# dcmotor_controller.net
KiCad netlist of a schematic drawn in EAGLE
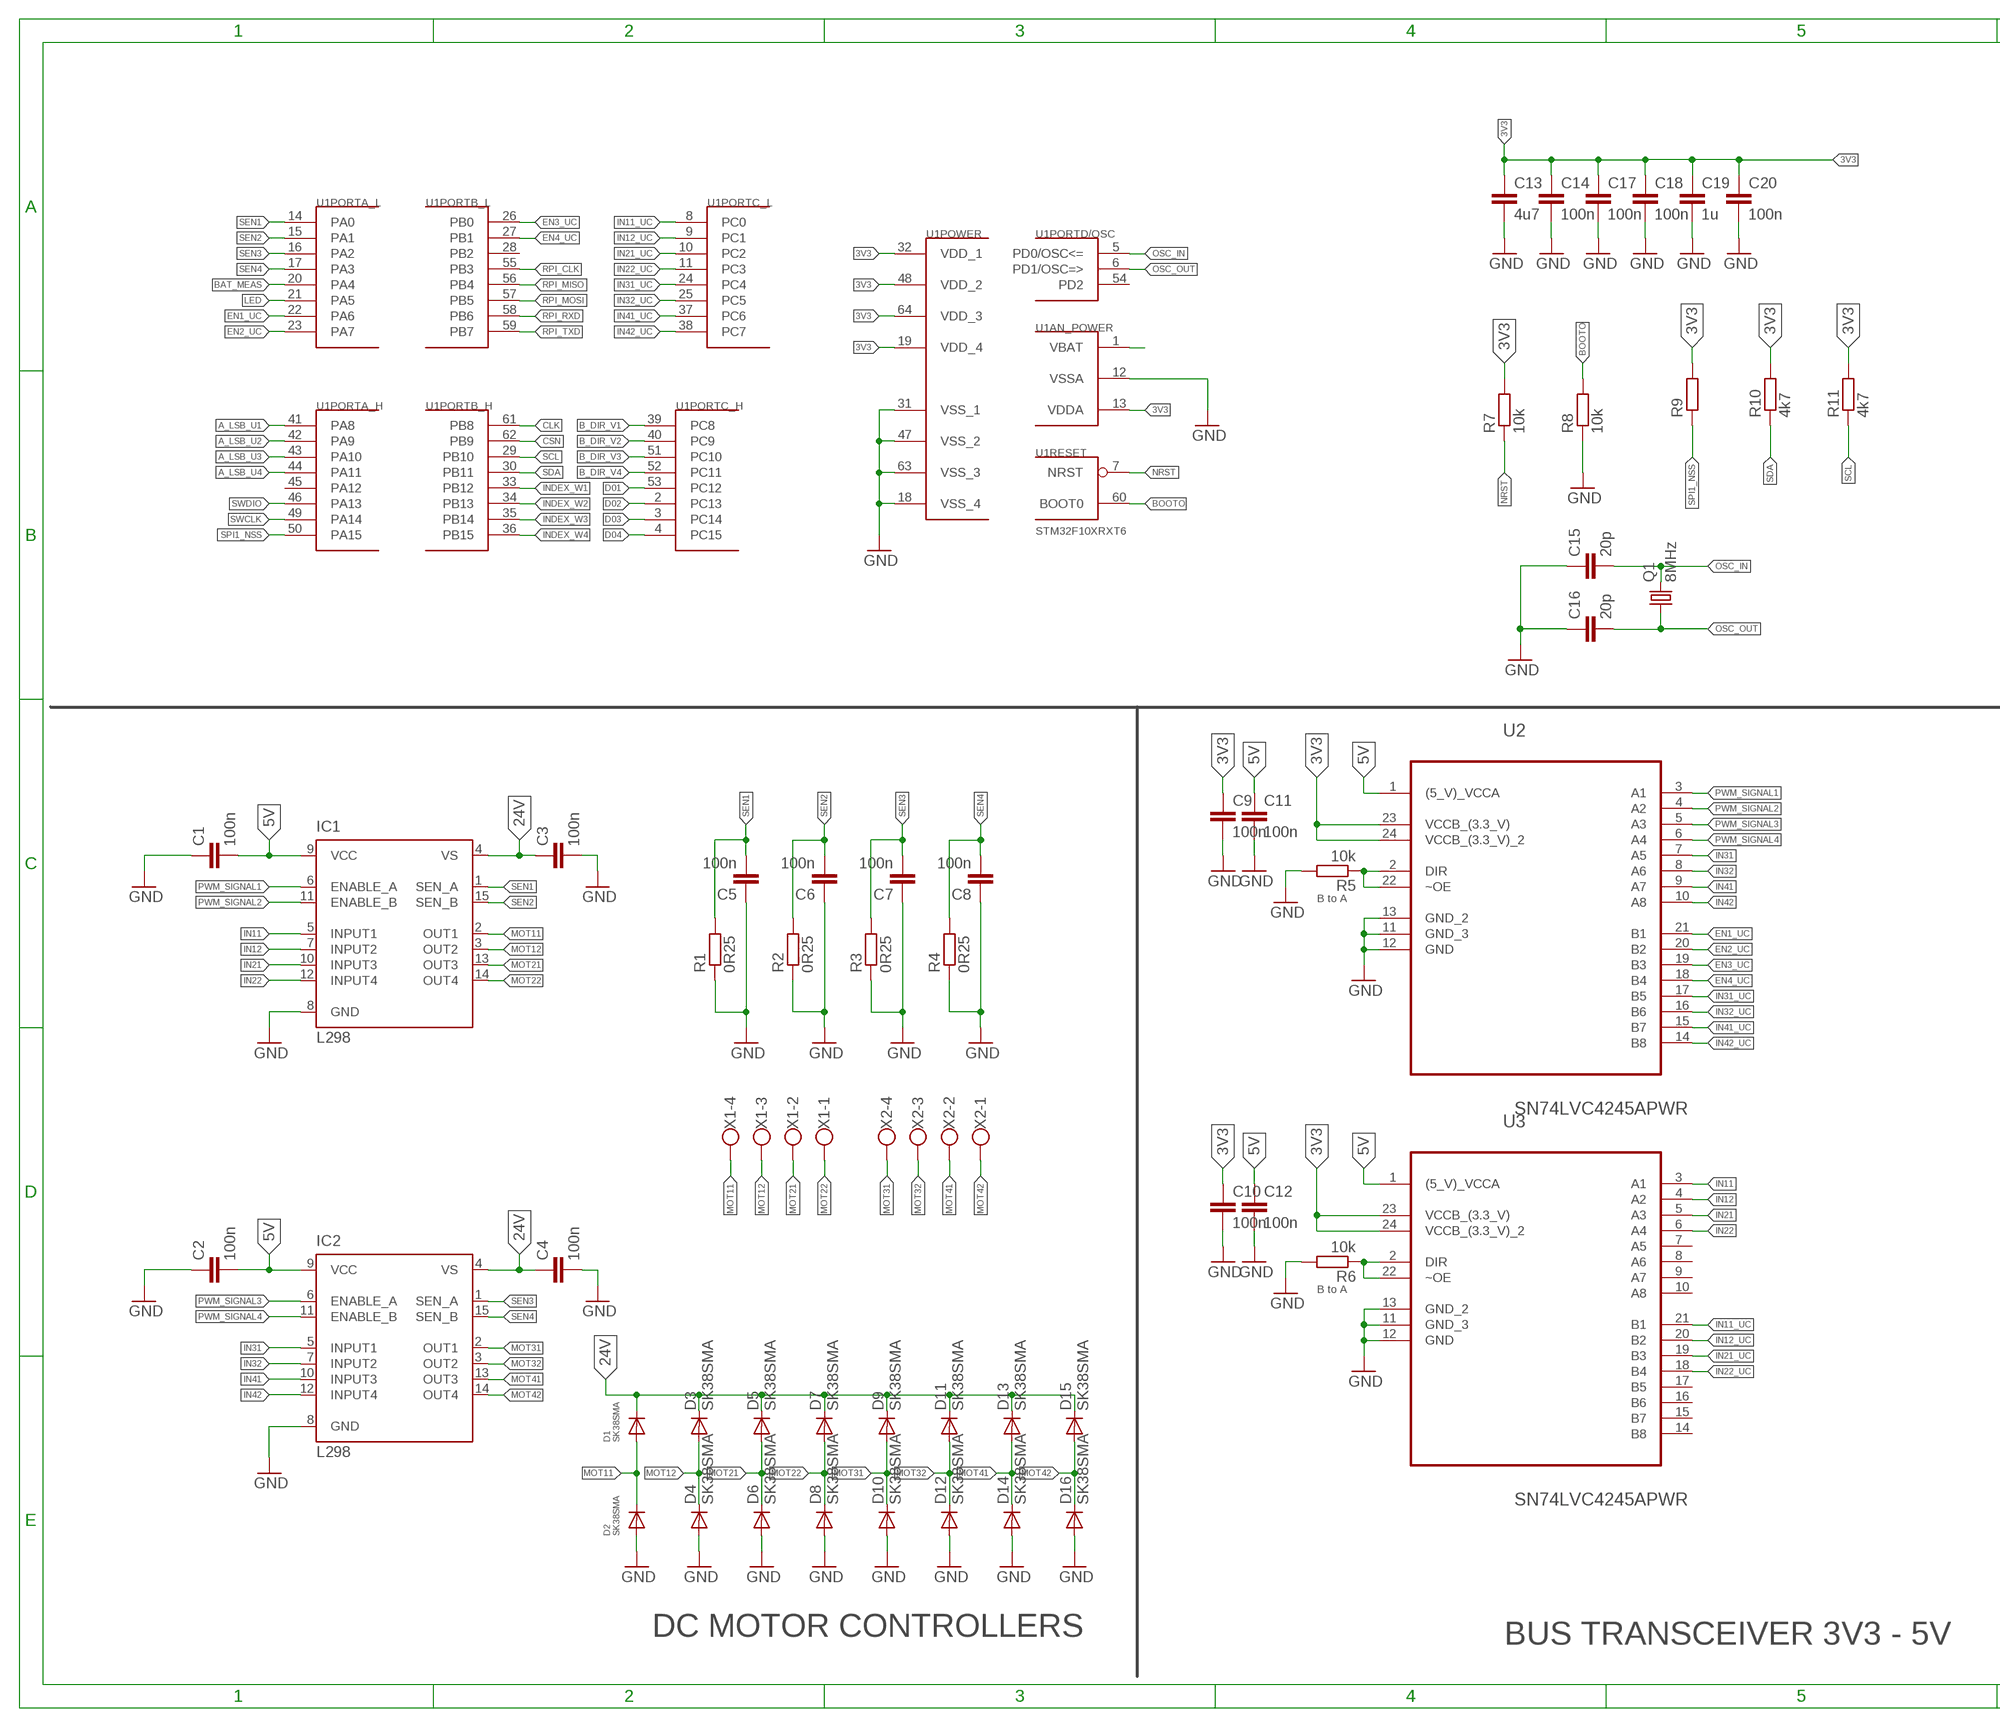
[diagram p0: schematic, sheet 1, part 1 of 2]
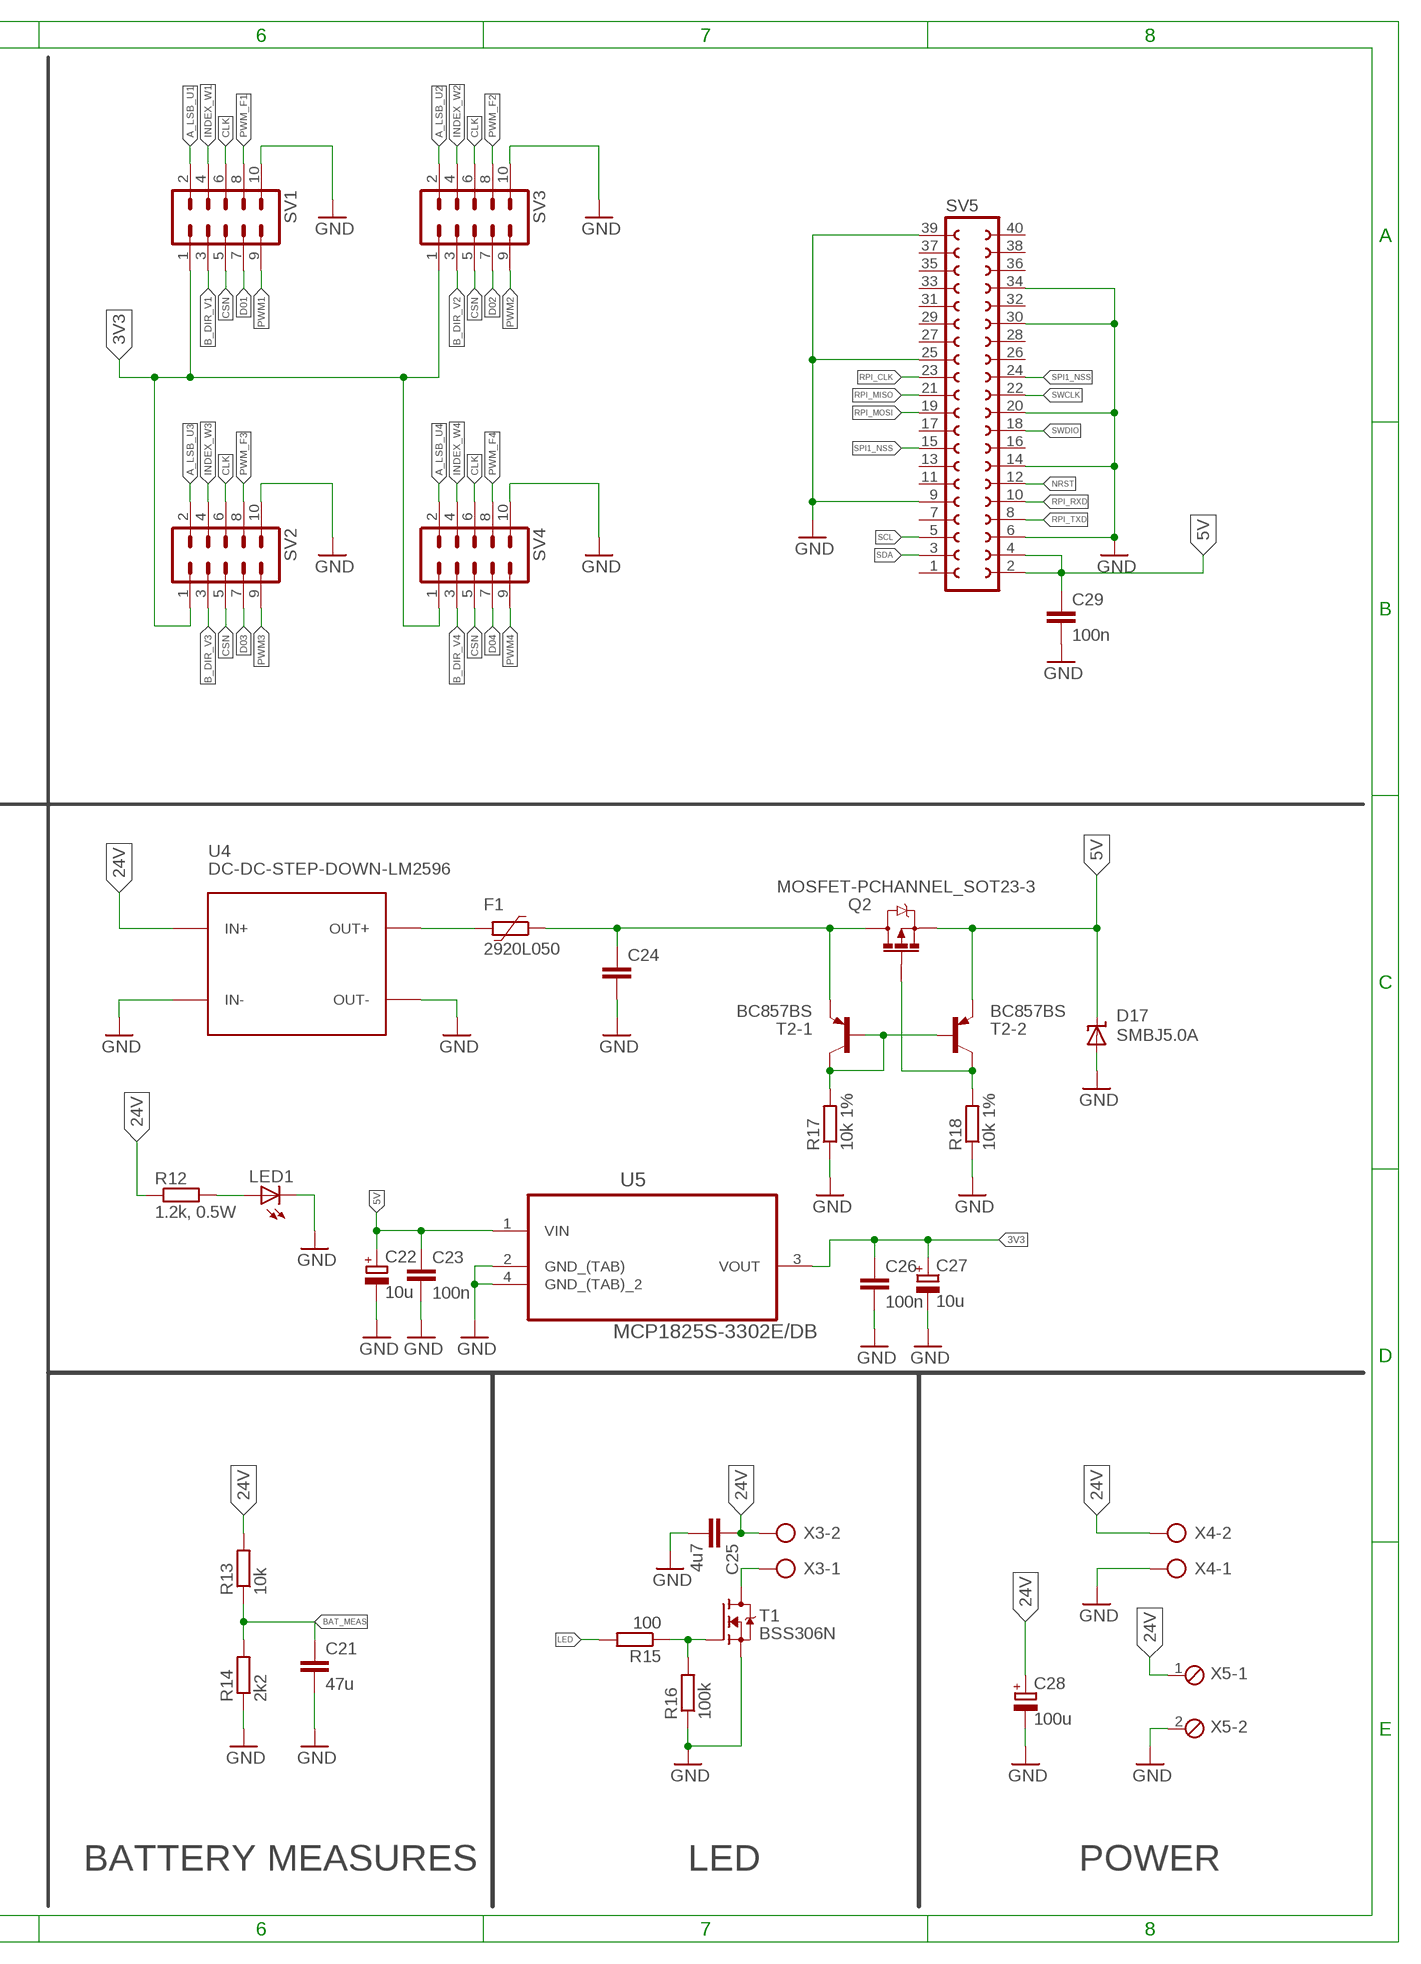
[diagram p1: schematic, sheet 1, part 2 of 2]

(export (version "E")
  (design (tool "Eeschema 10.0.6"))
  (components
    (comp (ref "C1")
      (value "100n")
      (footprint "eagle-import:C0805")
      (libsource (lib "eagle-import") (part "C-EUC0805"))
    )
    (comp (ref "C2")
      (value "100n")
      (footprint "eagle-import:C0805")
      (libsource (lib "eagle-import") (part "resistor_348_C-EUC0805"))
    )
    (comp (ref "C3")
      (value "100n")
      (footprint "eagle-import:C0805")
      (libsource (lib "eagle-import") (part "C-EUC0805"))
    )
    (comp (ref "C4")
      (value "100n")
      (footprint "eagle-import:C0805")
      (libsource (lib "eagle-import") (part "resistor_348_C-EUC0805"))
    )
    (comp (ref "C5")
      (value "100n")
      (footprint "eagle-import:C0805")
      (libsource (lib "eagle-import") (part "resistor_348_C-EUC0805"))
    )
    (comp (ref "C6")
      (value "100n")
      (footprint "eagle-import:C0805")
      (libsource (lib "eagle-import") (part "resistor_348_C-EUC0805"))
    )
    (comp (ref "C7")
      (value "100n")
      (footprint "eagle-import:C0805")
      (libsource (lib "eagle-import") (part "resistor_348_C-EUC0805"))
    )
    (comp (ref "C8")
      (value "100n")
      (footprint "eagle-import:C0805")
      (libsource (lib "eagle-import") (part "resistor_348_C-EUC0805"))
    )
    (comp (ref "C9")
      (value "100n")
      (footprint "eagle-import:C0805")
      (libsource (lib "eagle-import") (part "resistor_C-EUC0805"))
    )
    (comp (ref "C10")
      (value "100n")
      (footprint "eagle-import:C0805")
      (libsource (lib "eagle-import") (part "resistor_C-EUC0805"))
    )
    (comp (ref "C11")
      (value "100n")
      (footprint "eagle-import:C0805")
      (libsource (lib "eagle-import") (part "resistor_C-EUC0805"))
    )
    (comp (ref "C12")
      (value "100n")
      (footprint "eagle-import:C0805")
      (libsource (lib "eagle-import") (part "resistor_C-EUC0805"))
    )
    (comp (ref "C13")
      (value "4u7")
      (footprint "eagle-import:C0805")
      (libsource (lib "eagle-import") (part "C-EUC0805"))
    )
    (comp (ref "C14")
      (value "100n")
      (footprint "eagle-import:C0805")
      (libsource (lib "eagle-import") (part "C-EUC0805"))
    )
    (comp (ref "C15")
      (value "20p")
      (footprint "eagle-import:C0805")
      (libsource (lib "eagle-import") (part "C-EUC0805"))
    )
    (comp (ref "C16")
      (value "20p")
      (footprint "eagle-import:C0805")
      (libsource (lib "eagle-import") (part "C-EUC0805"))
    )
    (comp (ref "C17")
      (value "100n")
      (footprint "eagle-import:C0805")
      (libsource (lib "eagle-import") (part "C-EUC0805"))
    )
    (comp (ref "C18")
      (value "100n")
      (footprint "eagle-import:C0805")
      (libsource (lib "eagle-import") (part "C-EUC0805"))
    )
    (comp (ref "C19")
      (value "1u")
      (footprint "eagle-import:C0805")
      (libsource (lib "eagle-import") (part "C-EUC0805"))
    )
    (comp (ref "C20")
      (value "100n")
      (footprint "eagle-import:C0805")
      (libsource (lib "eagle-import") (part "C-EUC0805"))
    )
    (comp (ref "C21")
      (value "47u")
      (footprint "eagle-import:C0805")
      (libsource (lib "eagle-import") (part "resistor_348_C-EUC0805"))
    )
    (comp (ref "C22")
      (value "10u")
      (footprint "eagle-import:153CLV-0807")
      (libsource (lib "eagle-import") (part "CPOL-EU153CLV-0807"))
    )
    (comp (ref "C23")
      (value "100n")
      (footprint "eagle-import:C0805")
      (libsource (lib "eagle-import") (part "resistor_348_C-EUC0805"))
    )
    (comp (ref "C24")
      (value "C-EUC0805")
      (footprint "eagle-import:C0805")
      (libsource (lib "eagle-import") (part "C-EUC0805"))
    )
    (comp (ref "C25")
      (value "4u7")
      (footprint "eagle-import:C0805")
      (libsource (lib "eagle-import") (part "resistor_348_C-EUC0805"))
    )
    (comp (ref "C26")
      (value "100n")
      (footprint "eagle-import:C0805")
      (libsource (lib "eagle-import") (part "resistor_348_C-EUC0805"))
    )
    (comp (ref "C27")
      (value "10u")
      (footprint "eagle-import:153CLV-0807")
      (libsource (lib "eagle-import") (part "CPOL-EU153CLV-0807"))
    )
    (comp (ref "C28")
      (value "100u")
      (footprint "eagle-import:153CLV-0807")
      (libsource (lib "eagle-import") (part "CPOL-EU153CLV-0807"))
    )
    (comp (ref "C29")
      (value "100n")
      (footprint "eagle-import:C0805")
      (libsource (lib "eagle-import") (part "resistor_348_C-EUC0805"))
    )
    (comp (ref "D1")
      (value "SK38SMA")
      (footprint "eagle-import:DO214AC")
      (libsource (lib "eagle-import") (part "DIODE-DO214AC"))
    )
    (comp (ref "D2")
      (value "SK38SMA")
      (footprint "eagle-import:DO214AC")
      (libsource (lib "eagle-import") (part "DIODE-DO214AC"))
    )
    (comp (ref "D3")
      (value "SK38SMA")
      (footprint "eagle-import:DO214AC")
      (libsource (lib "eagle-import") (part "DIODE-DO214AC"))
    )
    (comp (ref "D4")
      (value "SK38SMA")
      (footprint "eagle-import:DO214AC")
      (libsource (lib "eagle-import") (part "DIODE-DO214AC"))
    )
    (comp (ref "D5")
      (value "SK38SMA")
      (footprint "eagle-import:DO214AC")
      (libsource (lib "eagle-import") (part "DIODE-DO214AC"))
    )
    (comp (ref "D6")
      (value "SK38SMA")
      (footprint "eagle-import:DO214AC")
      (libsource (lib "eagle-import") (part "DIODE-DO214AC"))
    )
    (comp (ref "D7")
      (value "SK38SMA")
      (footprint "eagle-import:DO214AC")
      (libsource (lib "eagle-import") (part "DIODE-DO214AC"))
    )
    (comp (ref "D8")
      (value "SK38SMA")
      (footprint "eagle-import:DO214AC")
      (libsource (lib "eagle-import") (part "DIODE-DO214AC"))
    )
    (comp (ref "D9")
      (value "SK38SMA")
      (footprint "eagle-import:DO214AC")
      (libsource (lib "eagle-import") (part "DIODE-DO214AC"))
    )
    (comp (ref "D10")
      (value "SK38SMA")
      (footprint "eagle-import:DO214AC")
      (libsource (lib "eagle-import") (part "DIODE-DO214AC"))
    )
    (comp (ref "D11")
      (value "SK38SMA")
      (footprint "eagle-import:DO214AC")
      (libsource (lib "eagle-import") (part "DIODE-DO214AC"))
    )
    (comp (ref "D12")
      (value "SK38SMA")
      (footprint "eagle-import:DO214AC")
      (libsource (lib "eagle-import") (part "DIODE-DO214AC"))
    )
    (comp (ref "D13")
      (value "SK38SMA")
      (footprint "eagle-import:DO214AC")
      (libsource (lib "eagle-import") (part "DIODE-DO214AC"))
    )
    (comp (ref "D14")
      (value "SK38SMA")
      (footprint "eagle-import:DO214AC")
      (libsource (lib "eagle-import") (part "DIODE-DO214AC"))
    )
    (comp (ref "D15")
      (value "SK38SMA")
      (footprint "eagle-import:DO214AC")
      (libsource (lib "eagle-import") (part "DIODE-DO214AC"))
    )
    (comp (ref "D16")
      (value "SK38SMA")
      (footprint "eagle-import:DO214AC")
      (libsource (lib "eagle-import") (part "DIODE-DO214AC"))
    )
    (comp (ref "D17")
      (value "SMBJ5.0A")
      (footprint "eagle-import:SMBJ")
      (libsource (lib "eagle-import") (part "SUPPRESSOR-SMBJ"))
    )
    (comp (ref "F1")
      (value "2920L050")
      (footprint "eagle-import:2920L")
      (fields (field (name "MF") "Littelfuse"))
      (libsource (lib "eagle-import") (part "?2920L050"))
    )
    (comp (ref "IC1")
      (value "L298")
      (footprint "eagle-import:MULTIWATT-15")
      (fields (field (name "MPN") "L298N"))
      (libsource (lib "eagle-import") (part "L298"))
    )
    (comp (ref "IC2")
      (value "L298")
      (footprint "eagle-import:MULTIWATT-15")
      (fields (field (name "MPN") "L298N"))
      (libsource (lib "eagle-import") (part "L298"))
    )
    (comp (ref "LED1")
      (value "LEDCHIPLED_0805")
      (footprint "eagle-import:CHIPLED_0805")
      (libsource (lib "eagle-import") (part "LEDCHIPLED_0805"))
    )
    (comp (ref "Q1")
      (value "8MHz")
      (footprint "eagle-import:CSM-7X-DU")
      (libsource (lib "eagle-import") (part "CSM-7X-DU"))
    )
    (comp (ref "Q2")
      (value "MOSFET-PCHANNEL_SOT23-3")
      (footprint "eagle-import:SOT23-3")
      (libsource (lib "eagle-import") (part "MOSFET-PCHANNEL_SOT23-3"))
    )
    (comp (ref "R1")
      (value "0R25")
      (footprint "eagle-import:R2512")
      (libsource (lib "eagle-import") (part "R-EU_R2512"))
    )
    (comp (ref "R2")
      (value "0R25")
      (footprint "eagle-import:R2512")
      (libsource (lib "eagle-import") (part "R-EU_R2512"))
    )
    (comp (ref "R3")
      (value "0R25")
      (footprint "eagle-import:R2512")
      (libsource (lib "eagle-import") (part "R-EU_R2512"))
    )
    (comp (ref "R4")
      (value "0R25")
      (footprint "eagle-import:R2512")
      (libsource (lib "eagle-import") (part "R-EU_R2512"))
    )
    (comp (ref "R5")
      (value "10k")
      (footprint "eagle-import:M0805")
      (libsource (lib "eagle-import") (part "resistor_R-EU_M0805"))
    )
    (comp (ref "R6")
      (value "10k")
      (footprint "eagle-import:M0805")
      (libsource (lib "eagle-import") (part "resistor_R-EU_M0805"))
    )
    (comp (ref "R7")
      (value "10k")
      (footprint "eagle-import:R0805")
      (libsource (lib "eagle-import") (part "rcl_334_R-EU_R0805"))
    )
    (comp (ref "R8")
      (value "10k")
      (footprint "eagle-import:R0805")
      (libsource (lib "eagle-import") (part "rcl_334_R-EU_R0805"))
    )
    (comp (ref "R9")
      (value "R-EU_R0805")
      (footprint "eagle-import:R0805")
      (libsource (lib "eagle-import") (part "rcl_334_R-EU_R0805"))
    )
    (comp (ref "R10")
      (value "4k7")
      (footprint "eagle-import:R0805")
      (libsource (lib "eagle-import") (part "rcl_334_R-EU_R0805"))
    )
    (comp (ref "R11")
      (value "4k7")
      (footprint "eagle-import:R0805")
      (libsource (lib "eagle-import") (part "rcl_334_R-EU_R0805"))
    )
    (comp (ref "R12")
      (value "1.2k, 0.5W")
      (footprint "eagle-import:R2010")
      (libsource (lib "eagle-import") (part "rcl_334_R-EU_R2010"))
    )
    (comp (ref "R13")
      (value "10k")
      (footprint "eagle-import:M0805")
      (libsource (lib "eagle-import") (part "resistor_348_R-EU_M0805"))
    )
    (comp (ref "R14")
      (value "2k2")
      (footprint "eagle-import:M0805")
      (libsource (lib "eagle-import") (part "resistor_348_R-EU_M0805"))
    )
    (comp (ref "R15")
      (value "100")
      (footprint "eagle-import:M0805")
      (libsource (lib "eagle-import") (part "resistor_348_R-EU_M0805"))
    )
    (comp (ref "R16")
      (value "100k")
      (footprint "eagle-import:M0805")
      (libsource (lib "eagle-import") (part "resistor_348_R-EU_M0805"))
    )
    (comp (ref "R17")
      (value "10k 1%")
      (footprint "eagle-import:M0805")
      (libsource (lib "eagle-import") (part "resistor_348_R-EU_M0805"))
    )
    (comp (ref "R18")
      (value "10k 1%")
      (footprint "eagle-import:M0805")
      (libsource (lib "eagle-import") (part "resistor_348_R-EU_M0805"))
    )
    (comp (ref "SV1")
      (value "ML10L")
      (footprint "eagle-import:ML10L")
      (libsource (lib "eagle-import") (part "ML10L"))
    )
    (comp (ref "SV2")
      (value "ML10L")
      (footprint "eagle-import:ML10L")
      (libsource (lib "eagle-import") (part "ML10L"))
    )
    (comp (ref "SV3")
      (value "ML10L")
      (footprint "eagle-import:ML10L")
      (libsource (lib "eagle-import") (part "ML10L"))
    )
    (comp (ref "SV4")
      (value "ML10L")
      (footprint "eagle-import:ML10L")
      (libsource (lib "eagle-import") (part "ML10L"))
    )
    (comp (ref "SV5")
      (value "FE20-2")
      (footprint "eagle-import:FE20-2")
      (libsource (lib "eagle-import") (part "FE20-2"))
    )
    (comp (ref "T1")
      (value "BSS306N")
      (footprint "eagle-import:SOT23")
      (libsource (lib "eagle-import") (part "MOSFET-N-SOT23"))
    )
    (comp (ref "T2")
      (value "BC857BS")
      (footprint "eagle-import:SOT363")
      (libsource (lib "eagle-import") (part "BC857BS"))
    )
    (comp (ref "U1")
      (value "STM32F10XRXT6")
      (footprint "eagle-import:TQFP64")
      (libsource (lib "eagle-import") (part "STM32F10XRXT6"))
    )
    (comp (ref "U2")
      (value "SN74LVC4245APWR")
      (footprint "eagle-import:SOP65P640X120-24N")
      (libsource (lib "eagle-import") (part "SN74LVC4245APWR"))
    )
    (comp (ref "U3")
      (value "SN74LVC4245APWR")
      (footprint "eagle-import:SOP65P640X120-24N")
      (libsource (lib "eagle-import") (part "SN74LVC4245APWR"))
    )
    (comp (ref "U4")
      (value "DC-DC-STEP-DOWN-LM2596")
      (footprint "eagle-import:DC-DC-STEP-DOWN-LM2596")
      (libsource (lib "eagle-import") (part "DC-DC-STEP-DOWN-LM2596"))
    )
    (comp (ref "U5")
      (value "MCP1825S-3302E/DB")
      (footprint "eagle-import:SOT230P700X180-4N")
      (fields (field (name "MF") "Microchip"))
      (libsource (lib "eagle-import") (part "MCP1825S-3302E/DB"))
    )
    (comp (ref "X1")
      (value "W237-4")
      (footprint "eagle-import:W237-4")
      (libsource (lib "eagle-import") (part "W237-4"))
    )
    (comp (ref "X2")
      (value "W237-4")
      (footprint "eagle-import:W237-4")
      (libsource (lib "eagle-import") (part "W237-4"))
    )
    (comp (ref "X3")
      (value "AK500/2")
      (footprint "eagle-import:AK500_2")
      (libsource (lib "eagle-import") (part "AK500/2"))
    )
    (comp (ref "X4")
      (value "AK500/2")
      (footprint "eagle-import:AK500_2")
      (libsource (lib "eagle-import") (part "AK500/2"))
    )
    (comp (ref "X5")
      (value "MPT2")
      (footprint "eagle-import:2POL254")
      (libsource (lib "eagle-import") (part "MPT2"))
    )
  )
  (nets
    (net (code "1") (name "3V3") (class "Default")
      (node (ref "C10") (pin "1") (pinfunction "1_1") (pintype "passive"))
      (node (ref "C13") (pin "1") (pinfunction "1_1") (pintype "passive"))
      (node (ref "C14") (pin "1") (pinfunction "1_1") (pintype "passive"))
      (node (ref "C17") (pin "1") (pinfunction "1_1") (pintype "passive"))
      (node (ref "C18") (pin "1") (pinfunction "1_1") (pintype "passive"))
      (node (ref "C19") (pin "1") (pinfunction "1_1") (pintype "passive"))
      (node (ref "C20") (pin "1") (pinfunction "1_1") (pintype "passive"))
      (node (ref "C26") (pin "1") (pinfunction "1_1") (pintype "passive"))
      (node (ref "C27") (pin "+") (pinfunction "+_+") (pintype "passive"))
      (node (ref "C9") (pin "1") (pinfunction "1_1") (pintype "passive"))
      (node (ref "R10") (pin "2") (pinfunction "2_2") (pintype "passive"))
      (node (ref "R11") (pin "2") (pinfunction "2_2") (pintype "passive"))
      (node (ref "R7") (pin "2") (pinfunction "2_2") (pintype "passive"))
      (node (ref "R9") (pin "2") (pinfunction "2_2") (pintype "passive"))
      (node (ref "SV1") (pin "1") (pinfunction "1_1") (pintype "passive"))
      (node (ref "SV2") (pin "1") (pinfunction "1_1") (pintype "passive"))
      (node (ref "SV3") (pin "1") (pinfunction "1_1") (pintype "passive"))
      (node (ref "SV4") (pin "1") (pinfunction "1_1") (pintype "passive"))
      (node (ref "U1") (pin "13") (pinfunction "VDDA_13") (pintype "power_in"))
      (node (ref "U1") (pin "19") (pinfunction "VDD_4_19") (pintype "power_in"))
      (node (ref "U1") (pin "32") (pinfunction "VDD_1_32") (pintype "power_in"))
      (node (ref "U1") (pin "48") (pinfunction "VDD_2_48") (pintype "power_in"))
      (node (ref "U1") (pin "64") (pinfunction "VDD_3_64") (pintype "power_in"))
      (node (ref "U2") (pin "23") (pinfunction "VCCB_(3.3_V)_23") (pintype "power_in"))
      (node (ref "U2") (pin "24") (pinfunction "VCCB_(3.3_V)_2_24") (pintype "power_in"))
      (node (ref "U3") (pin "23") (pinfunction "VCCB_(3.3_V)_23") (pintype "power_in"))
      (node (ref "U3") (pin "24") (pinfunction "VCCB_(3.3_V)_2_24") (pintype "power_in"))
      (node (ref "U5") (pin "3") (pinfunction "VOUT_3") (pintype "output"))
    )
    (net (code "2") (name "5V") (class "Default")
      (node (ref "C1") (pin "2") (pinfunction "2_2") (pintype "passive"))
      (node (ref "C11") (pin "1") (pinfunction "1_1") (pintype "passive"))
      (node (ref "C12") (pin "1") (pinfunction "1_1") (pintype "passive"))
      (node (ref "C2") (pin "2") (pinfunction "2_2") (pintype "passive"))
      (node (ref "C22") (pin "+") (pinfunction "+_+") (pintype "passive"))
      (node (ref "C23") (pin "1") (pinfunction "1_1") (pintype "passive"))
      (node (ref "C29") (pin "1") (pinfunction "1_1") (pintype "passive"))
      (node (ref "D17") (pin "C") (pinfunction "C_C") (pintype "passive"))
      (node (ref "IC1") (pin "9") (pinfunction "VCC_9") (pintype "power_in"))
      (node (ref "IC2") (pin "9") (pinfunction "VCC_9") (pintype "power_in"))
      (node (ref "Q2") (pin "2") (pinfunction "S_2") (pintype "passive"))
      (node (ref "SV5") (pin "2") (pinfunction "2_2") (pintype "passive"))
      (node (ref "SV5") (pin "4") (pinfunction "4_4") (pintype "passive"))
      (node (ref "T2") (pin "4") (pinfunction "E_4") (pintype "passive"))
      (node (ref "U2") (pin "1") (pinfunction "(5_V)_VCCA_1") (pintype "power_in"))
      (node (ref "U3") (pin "1") (pinfunction "(5_V)_VCCA_1") (pintype "power_in"))
      (node (ref "U5") (pin "1") (pinfunction "VIN_1") (pintype "input"))
    )
    (net (code "3") (name "24V") (class "Default")
      (node (ref "C25") (pin "1") (pinfunction "1_1") (pintype "passive"))
      (node (ref "C28") (pin "+") (pinfunction "+_+") (pintype "passive"))
      (node (ref "C3") (pin "1") (pinfunction "1_1") (pintype "passive"))
      (node (ref "C4") (pin "1") (pinfunction "1_1") (pintype "passive"))
      (node (ref "D1") (pin "C") (pinfunction "C_C") (pintype "passive"))
      (node (ref "D11") (pin "C") (pinfunction "C_C") (pintype "passive"))
      (node (ref "D13") (pin "C") (pinfunction "C_C") (pintype "passive"))
      (node (ref "D15") (pin "C") (pinfunction "C_C") (pintype "passive"))
      (node (ref "D3") (pin "C") (pinfunction "C_C") (pintype "passive"))
      (node (ref "D5") (pin "C") (pinfunction "C_C") (pintype "passive"))
      (node (ref "D7") (pin "C") (pinfunction "C_C") (pintype "passive"))
      (node (ref "D9") (pin "C") (pinfunction "C_C") (pintype "passive"))
      (node (ref "IC1") (pin "4") (pinfunction "VS_4") (pintype "power_in"))
      (node (ref "IC2") (pin "4") (pinfunction "VS_4") (pintype "power_in"))
      (node (ref "R12") (pin "1") (pinfunction "1_1") (pintype "passive"))
      (node (ref "R13") (pin "2") (pinfunction "2_2") (pintype "passive"))
      (node (ref "U4") (pin "IN+") (pinfunction "IN+_IN+") (pintype "bidirectional"))
      (node (ref "X3") (pin "2") (pinfunction "KL_2") (pintype "passive"))
      (node (ref "X4") (pin "2") (pinfunction "KL_2") (pintype "passive"))
      (node (ref "X5") (pin "1") (pinfunction "1_1") (pintype "passive"))
    )
    (net (code "4") (name "A_LSB_U1") (class "Default")
      (node (ref "SV1") (pin "2") (pinfunction "2_2") (pintype "passive"))
      (node (ref "U1") (pin "41") (pinfunction "PA8_41") (pintype "bidirectional"))
    )
    (net (code "5") (name "A_LSB_U2") (class "Default")
      (node (ref "SV3") (pin "2") (pinfunction "2_2") (pintype "passive"))
      (node (ref "U1") (pin "42") (pinfunction "PA9_42") (pintype "bidirectional"))
    )
    (net (code "6") (name "A_LSB_U3") (class "Default")
      (node (ref "SV2") (pin "2") (pinfunction "2_2") (pintype "passive"))
      (node (ref "U1") (pin "43") (pinfunction "PA10_43") (pintype "bidirectional"))
    )
    (net (code "7") (name "A_LSB_U4") (class "Default")
      (node (ref "SV4") (pin "2") (pinfunction "2_2") (pintype "passive"))
      (node (ref "U1") (pin "44") (pinfunction "PA11_44") (pintype "bidirectional"))
    )
    (net (code "8") (name "BAT_MEAS") (class "Default")
      (node (ref "C21") (pin "1") (pinfunction "1_1") (pintype "passive"))
      (node (ref "R13") (pin "1") (pinfunction "1_1") (pintype "passive"))
      (node (ref "R14") (pin "2") (pinfunction "2_2") (pintype "passive"))
      (node (ref "U1") (pin "20") (pinfunction "PA4_20") (pintype "bidirectional"))
    )
    (net (code "9") (name "BOOTO") (class "Default")
      (node (ref "R8") (pin "2") (pinfunction "2_2") (pintype "passive"))
      (node (ref "U1") (pin "60") (pinfunction "BOOT0_60") (pintype "input"))
    )
    (net (code "10") (name "B_DIR_V1") (class "Default")
      (node (ref "SV1") (pin "3") (pinfunction "3_3") (pintype "passive"))
      (node (ref "U1") (pin "39") (pinfunction "PC8_39") (pintype "bidirectional"))
    )
    (net (code "11") (name "B_DIR_V2") (class "Default")
      (node (ref "SV3") (pin "3") (pinfunction "3_3") (pintype "passive"))
      (node (ref "U1") (pin "40") (pinfunction "PC9_40") (pintype "bidirectional"))
    )
    (net (code "12") (name "B_DIR_V3") (class "Default")
      (node (ref "SV2") (pin "3") (pinfunction "3_3") (pintype "passive"))
      (node (ref "U1") (pin "51") (pinfunction "PC10_51") (pintype "bidirectional"))
    )
    (net (code "13") (name "B_DIR_V4") (class "Default")
      (node (ref "SV4") (pin "3") (pinfunction "3_3") (pintype "passive"))
      (node (ref "U1") (pin "52") (pinfunction "PC11_52") (pintype "bidirectional"))
    )
    (net (code "14") (name "CLK") (class "Default")
      (node (ref "SV1") (pin "6") (pinfunction "6_6") (pintype "passive"))
      (node (ref "SV2") (pin "6") (pinfunction "6_6") (pintype "passive"))
      (node (ref "SV3") (pin "6") (pinfunction "6_6") (pintype "passive"))
      (node (ref "SV4") (pin "6") (pinfunction "6_6") (pintype "passive"))
      (node (ref "U1") (pin "61") (pinfunction "PB8_61") (pintype "bidirectional"))
    )
    (net (code "15") (name "CSN") (class "Default")
      (node (ref "SV1") (pin "5") (pinfunction "5_5") (pintype "passive"))
      (node (ref "SV2") (pin "5") (pinfunction "5_5") (pintype "passive"))
      (node (ref "SV3") (pin "5") (pinfunction "5_5") (pintype "passive"))
      (node (ref "SV4") (pin "5") (pinfunction "5_5") (pintype "passive"))
      (node (ref "U1") (pin "62") (pinfunction "PB9_62") (pintype "bidirectional"))
    )
    (net (code "16") (name "D01") (class "Default")
      (node (ref "SV1") (pin "7") (pinfunction "7_7") (pintype "passive"))
      (node (ref "U1") (pin "53") (pinfunction "PC12_53") (pintype "bidirectional"))
    )
    (net (code "17") (name "D02") (class "Default")
      (node (ref "SV3") (pin "7") (pinfunction "7_7") (pintype "passive"))
      (node (ref "U1") (pin "2") (pinfunction "PC13_2") (pintype "bidirectional"))
    )
    (net (code "18") (name "D03") (class "Default")
      (node (ref "SV2") (pin "7") (pinfunction "7_7") (pintype "passive"))
      (node (ref "U1") (pin "3") (pinfunction "PC14_3") (pintype "bidirectional"))
    )
    (net (code "19") (name "D04") (class "Default")
      (node (ref "SV4") (pin "7") (pinfunction "7_7") (pintype "passive"))
      (node (ref "U1") (pin "4") (pinfunction "PC15_4") (pintype "bidirectional"))
    )
    (net (code "20") (name "EN1_UC") (class "Default")
      (node (ref "U1") (pin "22") (pinfunction "PA6_22") (pintype "bidirectional"))
      (node (ref "U2") (pin "21") (pinfunction "B1_21") (pintype "output"))
    )
    (net (code "21") (name "EN2_UC") (class "Default")
      (node (ref "U1") (pin "23") (pinfunction "PA7_23") (pintype "bidirectional"))
      (node (ref "U2") (pin "20") (pinfunction "B2_20") (pintype "output"))
    )
    (net (code "22") (name "EN3_UC") (class "Default")
      (node (ref "U1") (pin "26") (pinfunction "PB0_26") (pintype "bidirectional"))
      (node (ref "U2") (pin "19") (pinfunction "B3_19") (pintype "output"))
    )
    (net (code "23") (name "EN4_UC") (class "Default")
      (node (ref "U1") (pin "27") (pinfunction "PB1_27") (pintype "bidirectional"))
      (node (ref "U2") (pin "18") (pinfunction "B4_18") (pintype "output"))
    )
    (net (code "24") (name "GND") (class "Default")
      (node (ref "C1") (pin "1") (pinfunction "1_1") (pintype "passive"))
      (node (ref "C10") (pin "2") (pinfunction "2_2") (pintype "passive"))
      (node (ref "C11") (pin "2") (pinfunction "2_2") (pintype "passive"))
      (node (ref "C12") (pin "2") (pinfunction "2_2") (pintype "passive"))
      (node (ref "C13") (pin "2") (pinfunction "2_2") (pintype "passive"))
      (node (ref "C14") (pin "2") (pinfunction "2_2") (pintype "passive"))
      (node (ref "C15") (pin "1") (pinfunction "1_1") (pintype "passive"))
      (node (ref "C16") (pin "1") (pinfunction "1_1") (pintype "passive"))
      (node (ref "C17") (pin "2") (pinfunction "2_2") (pintype "passive"))
      (node (ref "C18") (pin "2") (pinfunction "2_2") (pintype "passive"))
      (node (ref "C19") (pin "2") (pinfunction "2_2") (pintype "passive"))
      (node (ref "C2") (pin "1") (pinfunction "1_1") (pintype "passive"))
      (node (ref "C20") (pin "2") (pinfunction "2_2") (pintype "passive"))
      (node (ref "C21") (pin "2") (pinfunction "2_2") (pintype "passive"))
      (node (ref "C22") (pin "-") (pinfunction "-_-") (pintype "passive"))
      (node (ref "C23") (pin "2") (pinfunction "2_2") (pintype "passive"))
      (node (ref "C24") (pin "2") (pinfunction "2_2") (pintype "passive"))
      (node (ref "C25") (pin "2") (pinfunction "2_2") (pintype "passive"))
      (node (ref "C26") (pin "2") (pinfunction "2_2") (pintype "passive"))
      (node (ref "C27") (pin "-") (pinfunction "-_-") (pintype "passive"))
      (node (ref "C28") (pin "-") (pinfunction "-_-") (pintype "passive"))
      (node (ref "C29") (pin "2") (pinfunction "2_2") (pintype "passive"))
      (node (ref "C3") (pin "2") (pinfunction "2_2") (pintype "passive"))
      (node (ref "C4") (pin "2") (pinfunction "2_2") (pintype "passive"))
      (node (ref "C5") (pin "1") (pinfunction "1_1") (pintype "passive"))
      (node (ref "C6") (pin "1") (pinfunction "1_1") (pintype "passive"))
      (node (ref "C7") (pin "1") (pinfunction "1_1") (pintype "passive"))
      (node (ref "C8") (pin "1") (pinfunction "1_1") (pintype "passive"))
      (node (ref "C9") (pin "2") (pinfunction "2_2") (pintype "passive"))
      (node (ref "D10") (pin "A") (pinfunction "A_A") (pintype "passive"))
      (node (ref "D12") (pin "A") (pinfunction "A_A") (pintype "passive"))
      (node (ref "D14") (pin "A") (pinfunction "A_A") (pintype "passive"))
      (node (ref "D16") (pin "A") (pinfunction "A_A") (pintype "passive"))
      (node (ref "D17") (pin "A") (pinfunction "A_A") (pintype "passive"))
      (node (ref "D2") (pin "A") (pinfunction "A_A") (pintype "passive"))
      (node (ref "D4") (pin "A") (pinfunction "A_A") (pintype "passive"))
      (node (ref "D6") (pin "A") (pinfunction "A_A") (pintype "passive"))
      (node (ref "D8") (pin "A") (pinfunction "A_A") (pintype "passive"))
      (node (ref "IC1") (pin "8") (pinfunction "GND_8") (pintype "power_in"))
      (node (ref "IC2") (pin "8") (pinfunction "GND_8") (pintype "power_in"))
      (node (ref "LED1") (pin "C") (pinfunction "C_C") (pintype "passive"))
      (node (ref "R1") (pin "1") (pinfunction "1_1") (pintype "passive"))
      (node (ref "R14") (pin "1") (pinfunction "1_1") (pintype "passive"))
      (node (ref "R16") (pin "1") (pinfunction "1_1") (pintype "passive"))
      (node (ref "R17") (pin "1") (pinfunction "1_1") (pintype "passive"))
      (node (ref "R18") (pin "1") (pinfunction "1_1") (pintype "passive"))
      (node (ref "R2") (pin "1") (pinfunction "1_1") (pintype "passive"))
      (node (ref "R3") (pin "1") (pinfunction "1_1") (pintype "passive"))
      (node (ref "R4") (pin "1") (pinfunction "1_1") (pintype "passive"))
      (node (ref "R5") (pin "2") (pinfunction "2_2") (pintype "passive"))
      (node (ref "R6") (pin "2") (pinfunction "2_2") (pintype "passive"))
      (node (ref "R8") (pin "1") (pinfunction "1_1") (pintype "passive"))
      (node (ref "SV1") (pin "10") (pinfunction "10_10") (pintype "passive"))
      (node (ref "SV2") (pin "10") (pinfunction "10_10") (pintype "passive"))
      (node (ref "SV3") (pin "10") (pinfunction "10_10") (pintype "passive"))
      (node (ref "SV4") (pin "10") (pinfunction "10_10") (pintype "passive"))
      (node (ref "SV5") (pin "14") (pinfunction "14_14") (pintype "passive"))
      (node (ref "SV5") (pin "20") (pinfunction "20_20") (pintype "passive"))
      (node (ref "SV5") (pin "25") (pinfunction "25_25") (pintype "passive"))
      (node (ref "SV5") (pin "30") (pinfunction "30_30") (pintype "passive"))
      (node (ref "SV5") (pin "34") (pinfunction "34_34") (pintype "passive"))
      (node (ref "SV5") (pin "39") (pinfunction "39_39") (pintype "passive"))
      (node (ref "SV5") (pin "6") (pinfunction "6_6") (pintype "passive"))
      (node (ref "SV5") (pin "9") (pinfunction "9_9") (pintype "passive"))
      (node (ref "T1") (pin "2") (pinfunction "S_2") (pintype "passive"))
      (node (ref "U1") (pin "12") (pinfunction "VSSA_12") (pintype "power_in"))
      (node (ref "U1") (pin "18") (pinfunction "VSS_4_18") (pintype "power_in"))
      (node (ref "U1") (pin "31") (pinfunction "VSS_1_31") (pintype "power_in"))
      (node (ref "U1") (pin "47") (pinfunction "VSS_2_47") (pintype "power_in"))
      (node (ref "U1") (pin "63") (pinfunction "VSS_3_63") (pintype "power_in"))
      (node (ref "U2") (pin "11") (pinfunction "GND_3_11") (pintype "passive"))
      (node (ref "U2") (pin "12") (pinfunction "GND_12") (pintype "passive"))
      (node (ref "U2") (pin "13") (pinfunction "GND_2_13") (pintype "passive"))
      (node (ref "U3") (pin "11") (pinfunction "GND_3_11") (pintype "passive"))
      (node (ref "U3") (pin "12") (pinfunction "GND_12") (pintype "passive"))
      (node (ref "U3") (pin "13") (pinfunction "GND_2_13") (pintype "passive"))
      (node (ref "U4") (pin "IN-") (pinfunction "IN-_IN-") (pintype "bidirectional"))
      (node (ref "U4") (pin "OUT-") (pinfunction "OUT-_OUT-") (pintype "bidirectional"))
      (node (ref "U5") (pin "2") (pinfunction "GND_(TAB)_2") (pintype "passive"))
      (node (ref "U5") (pin "4") (pinfunction "GND_(TAB)_2_4") (pintype "passive"))
      (node (ref "X4") (pin "1") (pinfunction "KL_1") (pintype "passive"))
      (node (ref "X5") (pin "2") (pinfunction "1_2") (pintype "passive"))
    )
    (net (code "25") (name "IN11") (class "Default")
      (node (ref "IC1") (pin "5") (pinfunction "INPUT1_5") (pintype "input"))
      (node (ref "U3") (pin "3") (pinfunction "A1_3") (pintype "output"))
    )
    (net (code "26") (name "IN11_UC") (class "Default")
      (node (ref "U1") (pin "8") (pinfunction "PC0_8") (pintype "bidirectional"))
      (node (ref "U3") (pin "21") (pinfunction "B1_21") (pintype "output"))
    )
    (net (code "27") (name "IN12") (class "Default")
      (node (ref "IC1") (pin "7") (pinfunction "INPUT2_7") (pintype "input"))
      (node (ref "U3") (pin "4") (pinfunction "A2_4") (pintype "output"))
    )
    (net (code "28") (name "IN12_UC") (class "Default")
      (node (ref "U1") (pin "9") (pinfunction "PC1_9") (pintype "bidirectional"))
      (node (ref "U3") (pin "20") (pinfunction "B2_20") (pintype "output"))
    )
    (net (code "29") (name "IN21") (class "Default")
      (node (ref "IC1") (pin "10") (pinfunction "INPUT3_10") (pintype "input"))
      (node (ref "U3") (pin "5") (pinfunction "A3_5") (pintype "output"))
    )
    (net (code "30") (name "IN21_UC") (class "Default")
      (node (ref "U1") (pin "10") (pinfunction "PC2_10") (pintype "bidirectional"))
      (node (ref "U3") (pin "19") (pinfunction "B3_19") (pintype "output"))
    )
    (net (code "31") (name "IN22") (class "Default")
      (node (ref "IC1") (pin "12") (pinfunction "INPUT4_12") (pintype "input"))
      (node (ref "U3") (pin "6") (pinfunction "A4_6") (pintype "output"))
    )
    (net (code "32") (name "IN22_UC") (class "Default")
      (node (ref "U1") (pin "11") (pinfunction "PC3_11") (pintype "bidirectional"))
      (node (ref "U3") (pin "18") (pinfunction "B4_18") (pintype "output"))
    )
    (net (code "33") (name "IN31") (class "Default")
      (node (ref "IC2") (pin "5") (pinfunction "INPUT1_5") (pintype "input"))
      (node (ref "U2") (pin "7") (pinfunction "A5_7") (pintype "output"))
    )
    (net (code "34") (name "IN31_UC") (class "Default")
      (node (ref "U1") (pin "24") (pinfunction "PC4_24") (pintype "bidirectional"))
      (node (ref "U2") (pin "17") (pinfunction "B5_17") (pintype "output"))
    )
    (net (code "35") (name "IN32") (class "Default")
      (node (ref "IC2") (pin "7") (pinfunction "INPUT2_7") (pintype "input"))
      (node (ref "U2") (pin "8") (pinfunction "A6_8") (pintype "output"))
    )
    (net (code "36") (name "IN32_UC") (class "Default")
      (node (ref "U1") (pin "25") (pinfunction "PC5_25") (pintype "bidirectional"))
      (node (ref "U2") (pin "16") (pinfunction "B6_16") (pintype "output"))
    )
    (net (code "37") (name "IN41") (class "Default")
      (node (ref "IC2") (pin "10") (pinfunction "INPUT3_10") (pintype "input"))
      (node (ref "U2") (pin "9") (pinfunction "A7_9") (pintype "output"))
    )
    (net (code "38") (name "IN41_UC") (class "Default")
      (node (ref "U1") (pin "37") (pinfunction "PC6_37") (pintype "bidirectional"))
      (node (ref "U2") (pin "15") (pinfunction "B7_15") (pintype "output"))
    )
    (net (code "39") (name "IN42") (class "Default")
      (node (ref "IC2") (pin "12") (pinfunction "INPUT4_12") (pintype "input"))
      (node (ref "U2") (pin "10") (pinfunction "A8_10") (pintype "output"))
    )
    (net (code "40") (name "IN42_UC") (class "Default")
      (node (ref "U1") (pin "38") (pinfunction "PC7_38") (pintype "bidirectional"))
      (node (ref "U2") (pin "14") (pinfunction "B8_14") (pintype "output"))
    )
    (net (code "41") (name "INDEX_W1") (class "Default")
      (node (ref "SV1") (pin "4") (pinfunction "4_4") (pintype "passive"))
      (node (ref "U1") (pin "33") (pinfunction "PB12_33") (pintype "bidirectional"))
    )
    (net (code "42") (name "INDEX_W2") (class "Default")
      (node (ref "SV3") (pin "4") (pinfunction "4_4") (pintype "passive"))
      (node (ref "U1") (pin "34") (pinfunction "PB13_34") (pintype "bidirectional"))
    )
    (net (code "43") (name "INDEX_W3") (class "Default")
      (node (ref "SV2") (pin "4") (pinfunction "4_4") (pintype "passive"))
      (node (ref "U1") (pin "35") (pinfunction "PB14_35") (pintype "bidirectional"))
    )
    (net (code "44") (name "INDEX_W4") (class "Default")
      (node (ref "SV4") (pin "4") (pinfunction "4_4") (pintype "passive"))
      (node (ref "U1") (pin "36") (pinfunction "PB15_36") (pintype "bidirectional"))
    )
    (net (code "45") (name "LED") (class "Default")
      (node (ref "R15") (pin "2") (pinfunction "2_2") (pintype "passive"))
      (node (ref "U1") (pin "21") (pinfunction "PA5_21") (pintype "bidirectional"))
    )
    (net (code "46") (name "MOT11") (class "Default")
      (node (ref "D1") (pin "A") (pinfunction "A_A") (pintype "passive"))
      (node (ref "D2") (pin "C") (pinfunction "C_C") (pintype "passive"))
      (node (ref "IC1") (pin "2") (pinfunction "OUT1_2") (pintype "output"))
      (node (ref "X1") (pin "4") (pinfunction "KL_4") (pintype "passive"))
    )
    (net (code "47") (name "MOT12") (class "Default")
      (node (ref "D3") (pin "A") (pinfunction "A_A") (pintype "passive"))
      (node (ref "D4") (pin "C") (pinfunction "C_C") (pintype "passive"))
      (node (ref "IC1") (pin "3") (pinfunction "OUT2_3") (pintype "output"))
      (node (ref "X1") (pin "3") (pinfunction "KL_3") (pintype "passive"))
    )
    (net (code "48") (name "MOT21") (class "Default")
      (node (ref "D5") (pin "A") (pinfunction "A_A") (pintype "passive"))
      (node (ref "D6") (pin "C") (pinfunction "C_C") (pintype "passive"))
      (node (ref "IC1") (pin "13") (pinfunction "OUT3_13") (pintype "output"))
      (node (ref "X1") (pin "2") (pinfunction "KL_2") (pintype "passive"))
    )
    (net (code "49") (name "MOT22") (class "Default")
      (node (ref "D7") (pin "A") (pinfunction "A_A") (pintype "passive"))
      (node (ref "D8") (pin "C") (pinfunction "C_C") (pintype "passive"))
      (node (ref "IC1") (pin "14") (pinfunction "OUT4_14") (pintype "output"))
      (node (ref "X1") (pin "1") (pinfunction "KL_1") (pintype "passive"))
    )
    (net (code "50") (name "MOT31") (class "Default")
      (node (ref "D10") (pin "C") (pinfunction "C_C") (pintype "passive"))
      (node (ref "D9") (pin "A") (pinfunction "A_A") (pintype "passive"))
      (node (ref "IC2") (pin "2") (pinfunction "OUT1_2") (pintype "output"))
      (node (ref "X2") (pin "4") (pinfunction "KL_4") (pintype "passive"))
    )
    (net (code "51") (name "MOT32") (class "Default")
      (node (ref "D11") (pin "A") (pinfunction "A_A") (pintype "passive"))
      (node (ref "D12") (pin "C") (pinfunction "C_C") (pintype "passive"))
      (node (ref "IC2") (pin "3") (pinfunction "OUT2_3") (pintype "output"))
      (node (ref "X2") (pin "3") (pinfunction "KL_3") (pintype "passive"))
    )
    (net (code "52") (name "MOT41") (class "Default")
      (node (ref "D13") (pin "A") (pinfunction "A_A") (pintype "passive"))
      (node (ref "D14") (pin "C") (pinfunction "C_C") (pintype "passive"))
      (node (ref "IC2") (pin "13") (pinfunction "OUT3_13") (pintype "output"))
      (node (ref "X2") (pin "2") (pinfunction "KL_2") (pintype "passive"))
    )
    (net (code "53") (name "MOT42") (class "Default")
      (node (ref "D15") (pin "A") (pinfunction "A_A") (pintype "passive"))
      (node (ref "D16") (pin "C") (pinfunction "C_C") (pintype "passive"))
      (node (ref "IC2") (pin "14") (pinfunction "OUT4_14") (pintype "output"))
      (node (ref "X2") (pin "1") (pinfunction "KL_1") (pintype "passive"))
    )
    (net (code "54") (name "NRST") (class "Default")
      (node (ref "R7") (pin "1") (pinfunction "1_1") (pintype "passive"))
      (node (ref "SV5") (pin "12") (pinfunction "12_12") (pintype "passive"))
      (node (ref "U1") (pin "7") (pinfunction "NRST_7") (pintype "input"))
    )
    (net (code "55") (name "Net-(F1-Pad2)") (class "Default")
      (node (ref "F1") (pin "2") (pinfunction "2_2") (pintype "passive"))
      (node (ref "U4") (pin "OUT+") (pinfunction "OUT+_OUT+") (pintype "bidirectional"))
    )
    (net (code "56") (name "Net-(LED1-PadA)") (class "Default")
      (node (ref "LED1") (pin "A") (pinfunction "A_A") (pintype "passive"))
      (node (ref "R12") (pin "2") (pinfunction "2_2") (pintype "passive"))
    )
    (net (code "57") (name "Net-(Q2-D)") (class "Default")
      (node (ref "C24") (pin "1") (pinfunction "1_1") (pintype "passive"))
      (node (ref "F1") (pin "1") (pinfunction "1_1") (pintype "passive"))
      (node (ref "Q2") (pin "3") (pinfunction "D_3") (pintype "passive"))
      (node (ref "T2") (pin "1") (pinfunction "E_1") (pintype "passive"))
    )
    (net (code "58") (name "Net-(Q2-G)") (class "Default")
      (node (ref "Q2") (pin "1") (pinfunction "G_1") (pintype "passive"))
      (node (ref "R18") (pin "2") (pinfunction "2_2") (pintype "passive"))
      (node (ref "T2") (pin "3") (pinfunction "C_3") (pintype "passive"))
    )
    (net (code "59") (name "Net-(T1-D)") (class "Default")
      (node (ref "T1") (pin "3") (pinfunction "D_3") (pintype "passive"))
      (node (ref "X3") (pin "1") (pinfunction "KL_1") (pintype "passive"))
    )
    (net (code "60") (name "Net-(T1-G)") (class "Default")
      (node (ref "R15") (pin "1") (pinfunction "1_1") (pintype "passive"))
      (node (ref "R16") (pin "2") (pinfunction "2_2") (pintype "passive"))
      (node (ref "T1") (pin "1") (pinfunction "G_1") (pintype "passive"))
    )
    (net (code "61") (name "Net-(T2A-B)") (class "Default")
      (node (ref "R17") (pin "2") (pinfunction "2_2") (pintype "passive"))
      (node (ref "T2") (pin "2") (pinfunction "B_2") (pintype "passive"))
      (node (ref "T2") (pin "5") (pinfunction "B_5") (pintype "passive"))
      (node (ref "T2") (pin "6") (pinfunction "C_6") (pintype "passive"))
    )
    (net (code "62") (name "Net-(U2-DIR)") (class "Default")
      (node (ref "R5") (pin "1") (pinfunction "1_1") (pintype "passive"))
      (node (ref "U2") (pin "2") (pinfunction "DIR_2") (pintype "input"))
      (node (ref "U2") (pin "22") (pinfunction "~{OE}_22") (pintype "input"))
    )
    (net (code "63") (name "Net-(U3-DIR)") (class "Default")
      (node (ref "R6") (pin "1") (pinfunction "1_1") (pintype "passive"))
      (node (ref "U3") (pin "2") (pinfunction "DIR_2") (pintype "input"))
      (node (ref "U3") (pin "22") (pinfunction "~{OE}_22") (pintype "input"))
    )
    (net (code "64") (name "OSC_IN") (class "Default")
      (node (ref "C15") (pin "2") (pinfunction "2_2") (pintype "passive"))
      (node (ref "Q1") (pin "2") (pinfunction "2_2") (pintype "passive"))
      (node (ref "U1") (pin "5") (pinfunction "PD0/OSC<=_5") (pintype "bidirectional"))
    )
    (net (code "65") (name "OSC_OUT") (class "Default")
      (node (ref "C16") (pin "2") (pinfunction "2_2") (pintype "passive"))
      (node (ref "Q1") (pin "1") (pinfunction "1_1") (pintype "passive"))
      (node (ref "U1") (pin "6") (pinfunction "PD1/OSC=>_6") (pintype "bidirectional"))
    )
    (net (code "66") (name "PWM1") (class "Default")
      (node (ref "SV1") (pin "9") (pinfunction "9_9") (pintype "passive"))
    )
    (net (code "67") (name "PWM2") (class "Default")
      (node (ref "SV3") (pin "9") (pinfunction "9_9") (pintype "passive"))
    )
    (net (code "68") (name "PWM3") (class "Default")
      (node (ref "SV2") (pin "9") (pinfunction "9_9") (pintype "passive"))
    )
    (net (code "69") (name "PWM4") (class "Default")
      (node (ref "SV4") (pin "9") (pinfunction "9_9") (pintype "passive"))
    )
    (net (code "70") (name "PWM_F1") (class "Default")
      (node (ref "SV1") (pin "8") (pinfunction "8_8") (pintype "passive"))
    )
    (net (code "71") (name "PWM_F2") (class "Default")
      (node (ref "SV3") (pin "8") (pinfunction "8_8") (pintype "passive"))
    )
    (net (code "72") (name "PWM_F3") (class "Default")
      (node (ref "SV2") (pin "8") (pinfunction "8_8") (pintype "passive"))
    )
    (net (code "73") (name "PWM_F4") (class "Default")
      (node (ref "SV4") (pin "8") (pinfunction "8_8") (pintype "passive"))
    )
    (net (code "74") (name "PWM_SIGNAL1") (class "Default")
      (node (ref "IC1") (pin "6") (pinfunction "ENABLE_A_6") (pintype "input"))
      (node (ref "U2") (pin "3") (pinfunction "A1_3") (pintype "output"))
    )
    (net (code "75") (name "PWM_SIGNAL2") (class "Default")
      (node (ref "IC1") (pin "11") (pinfunction "ENABLE_B_11") (pintype "input"))
      (node (ref "U2") (pin "4") (pinfunction "A2_4") (pintype "output"))
    )
    (net (code "76") (name "PWM_SIGNAL3") (class "Default")
      (node (ref "IC2") (pin "6") (pinfunction "ENABLE_A_6") (pintype "input"))
      (node (ref "U2") (pin "5") (pinfunction "A3_5") (pintype "output"))
    )
    (net (code "77") (name "PWM_SIGNAL4") (class "Default")
      (node (ref "IC2") (pin "11") (pinfunction "ENABLE_B_11") (pintype "input"))
      (node (ref "U2") (pin "6") (pinfunction "A4_6") (pintype "output"))
    )
    (net (code "78") (name "RPI_CLK") (class "Default")
      (node (ref "SV5") (pin "23") (pinfunction "23_23") (pintype "passive"))
      (node (ref "U1") (pin "55") (pinfunction "PB3_55") (pintype "bidirectional"))
    )
    (net (code "79") (name "RPI_MISO") (class "Default")
      (node (ref "SV5") (pin "21") (pinfunction "21_21") (pintype "passive"))
      (node (ref "U1") (pin "56") (pinfunction "PB4_56") (pintype "bidirectional"))
    )
    (net (code "80") (name "RPI_MOSI") (class "Default")
      (node (ref "SV5") (pin "19") (pinfunction "19_19") (pintype "passive"))
      (node (ref "U1") (pin "57") (pinfunction "PB5_57") (pintype "bidirectional"))
    )
    (net (code "81") (name "RPI_RXD") (class "Default")
      (node (ref "SV5") (pin "10") (pinfunction "10_10") (pintype "passive"))
      (node (ref "U1") (pin "58") (pinfunction "PB6_58") (pintype "bidirectional"))
    )
    (net (code "82") (name "RPI_TXD") (class "Default")
      (node (ref "SV5") (pin "8") (pinfunction "8_8") (pintype "passive"))
      (node (ref "U1") (pin "59") (pinfunction "PB7_59") (pintype "bidirectional"))
    )
    (net (code "83") (name "SCL") (class "Default")
      (node (ref "R11") (pin "1") (pinfunction "1_1") (pintype "passive"))
      (node (ref "SV5") (pin "5") (pinfunction "5_5") (pintype "passive"))
      (node (ref "U1") (pin "29") (pinfunction "PB10_29") (pintype "bidirectional"))
    )
    (net (code "84") (name "SDA") (class "Default")
      (node (ref "R10") (pin "1") (pinfunction "1_1") (pintype "passive"))
      (node (ref "SV5") (pin "3") (pinfunction "3_3") (pintype "passive"))
      (node (ref "U1") (pin "30") (pinfunction "PB11_30") (pintype "bidirectional"))
    )
    (net (code "85") (name "SEN1") (class "Default")
      (node (ref "C5") (pin "2") (pinfunction "2_2") (pintype "passive"))
      (node (ref "IC1") (pin "1") (pinfunction "SEN_A_1") (pintype "input"))
      (node (ref "R1") (pin "2") (pinfunction "2_2") (pintype "passive"))
      (node (ref "U1") (pin "14") (pinfunction "PA0_14") (pintype "bidirectional"))
    )
    (net (code "86") (name "SEN2") (class "Default")
      (node (ref "C6") (pin "2") (pinfunction "2_2") (pintype "passive"))
      (node (ref "IC1") (pin "15") (pinfunction "SEN_B_15") (pintype "input"))
      (node (ref "R2") (pin "2") (pinfunction "2_2") (pintype "passive"))
      (node (ref "U1") (pin "15") (pinfunction "PA1_15") (pintype "bidirectional"))
    )
    (net (code "87") (name "SEN3") (class "Default")
      (node (ref "C7") (pin "2") (pinfunction "2_2") (pintype "passive"))
      (node (ref "IC2") (pin "1") (pinfunction "SEN_A_1") (pintype "input"))
      (node (ref "R3") (pin "2") (pinfunction "2_2") (pintype "passive"))
      (node (ref "U1") (pin "16") (pinfunction "PA2_16") (pintype "bidirectional"))
    )
    (net (code "88") (name "SEN4") (class "Default")
      (node (ref "C8") (pin "2") (pinfunction "2_2") (pintype "passive"))
      (node (ref "IC2") (pin "15") (pinfunction "SEN_B_15") (pintype "input"))
      (node (ref "R4") (pin "2") (pinfunction "2_2") (pintype "passive"))
      (node (ref "U1") (pin "17") (pinfunction "PA3_17") (pintype "bidirectional"))
    )
    (net (code "89") (name "SPI1_NSS") (class "Default")
      (node (ref "R9") (pin "1") (pinfunction "1_1") (pintype "passive"))
      (node (ref "SV5") (pin "15") (pinfunction "15_15") (pintype "passive"))
      (node (ref "SV5") (pin "24") (pinfunction "24_24") (pintype "passive"))
      (node (ref "U1") (pin "50") (pinfunction "PA15_50") (pintype "bidirectional"))
    )
    (net (code "90") (name "SWCLK") (class "Default")
      (node (ref "SV5") (pin "22") (pinfunction "22_22") (pintype "passive"))
      (node (ref "U1") (pin "49") (pinfunction "PA14_49") (pintype "bidirectional"))
    )
    (net (code "91") (name "SWDIO") (class "Default")
      (node (ref "SV5") (pin "18") (pinfunction "18_18") (pintype "passive"))
      (node (ref "U1") (pin "46") (pinfunction "PA13_46") (pintype "bidirectional"))
    )
    (net (code "92") (name "unconnected-(SV5-Pad1)") (class "Default")
      (node (ref "SV5") (pin "1") (pinfunction "1_1") (pintype "passive"))
    )
    (net (code "93") (name "unconnected-(SV5-Pad7)") (class "Default")
      (node (ref "SV5") (pin "7") (pinfunction "7_7") (pintype "passive"))
    )
    (net (code "94") (name "unconnected-(SV5-Pad11)") (class "Default")
      (node (ref "SV5") (pin "11") (pinfunction "11_11") (pintype "passive"))
    )
    (net (code "95") (name "unconnected-(SV5-Pad13)") (class "Default")
      (node (ref "SV5") (pin "13") (pinfunction "13_13") (pintype "passive"))
    )
    (net (code "96") (name "unconnected-(SV5-Pad16)") (class "Default")
      (node (ref "SV5") (pin "16") (pinfunction "16_16") (pintype "passive"))
    )
    (net (code "97") (name "unconnected-(SV5-Pad17)") (class "Default")
      (node (ref "SV5") (pin "17") (pinfunction "17_17") (pintype "passive"))
    )
    (net (code "98") (name "unconnected-(SV5-Pad26)") (class "Default")
      (node (ref "SV5") (pin "26") (pinfunction "26_26") (pintype "passive"))
    )
    (net (code "99") (name "unconnected-(SV5-Pad27)") (class "Default")
      (node (ref "SV5") (pin "27") (pinfunction "27_27") (pintype "passive"))
    )
    (net (code "100") (name "unconnected-(SV5-Pad28)") (class "Default")
      (node (ref "SV5") (pin "28") (pinfunction "28_28") (pintype "passive"))
    )
    (net (code "101") (name "unconnected-(SV5-Pad29)") (class "Default")
      (node (ref "SV5") (pin "29") (pinfunction "29_29") (pintype "passive"))
    )
    (net (code "102") (name "unconnected-(SV5-Pad31)") (class "Default")
      (node (ref "SV5") (pin "31") (pinfunction "31_31") (pintype "passive"))
    )
    (net (code "103") (name "unconnected-(SV5-Pad32)") (class "Default")
      (node (ref "SV5") (pin "32") (pinfunction "32_32") (pintype "passive"))
    )
    (net (code "104") (name "unconnected-(SV5-Pad33)") (class "Default")
      (node (ref "SV5") (pin "33") (pinfunction "33_33") (pintype "passive"))
    )
    (net (code "105") (name "unconnected-(SV5-Pad35)") (class "Default")
      (node (ref "SV5") (pin "35") (pinfunction "35_35") (pintype "passive"))
    )
    (net (code "106") (name "unconnected-(SV5-Pad36)") (class "Default")
      (node (ref "SV5") (pin "36") (pinfunction "36_36") (pintype "passive"))
    )
    (net (code "107") (name "unconnected-(SV5-Pad37)") (class "Default")
      (node (ref "SV5") (pin "37") (pinfunction "37_37") (pintype "passive"))
    )
    (net (code "108") (name "unconnected-(SV5-Pad38)") (class "Default")
      (node (ref "SV5") (pin "38") (pinfunction "38_38") (pintype "passive"))
    )
    (net (code "109") (name "unconnected-(SV5-Pad40)") (class "Default")
      (node (ref "SV5") (pin "40") (pinfunction "40_40") (pintype "passive"))
    )
    (net (code "110") (name "unconnected-(U1A-VBAT-Pad1)") (class "Default")
      (node (ref "U1") (pin "1") (pinfunction "VBAT_1") (pintype "power_in"))
    )
    (net (code "111") (name "unconnected-(U1B-PA12-Pad45)") (class "Default")
      (node (ref "U1") (pin "45") (pinfunction "PA12_45") (pintype "bidirectional"))
    )
    (net (code "112") (name "unconnected-(U1E-PB2-Pad28)") (class "Default")
      (node (ref "U1") (pin "28") (pinfunction "PB2_28") (pintype "bidirectional"))
    )
    (net (code "113") (name "unconnected-(U1H-PD2-Pad54)") (class "Default")
      (node (ref "U1") (pin "54") (pinfunction "PD2_54") (pintype "bidirectional"))
    )
    (net (code "114") (name "unconnected-(U3-A5-Pad7)") (class "Default")
      (node (ref "U3") (pin "7") (pinfunction "A5_7") (pintype "output"))
    )
    (net (code "115") (name "unconnected-(U3-A6-Pad8)") (class "Default")
      (node (ref "U3") (pin "8") (pinfunction "A6_8") (pintype "output"))
    )
    (net (code "116") (name "unconnected-(U3-A7-Pad9)") (class "Default")
      (node (ref "U3") (pin "9") (pinfunction "A7_9") (pintype "output"))
    )
    (net (code "117") (name "unconnected-(U3-A8-Pad10)") (class "Default")
      (node (ref "U3") (pin "10") (pinfunction "A8_10") (pintype "output"))
    )
    (net (code "118") (name "unconnected-(U3-B5-Pad17)") (class "Default")
      (node (ref "U3") (pin "17") (pinfunction "B5_17") (pintype "output"))
    )
    (net (code "119") (name "unconnected-(U3-B6-Pad16)") (class "Default")
      (node (ref "U3") (pin "16") (pinfunction "B6_16") (pintype "output"))
    )
    (net (code "120") (name "unconnected-(U3-B7-Pad15)") (class "Default")
      (node (ref "U3") (pin "15") (pinfunction "B7_15") (pintype "output"))
    )
    (net (code "121") (name "unconnected-(U3-B8-Pad14)") (class "Default")
      (node (ref "U3") (pin "14") (pinfunction "B8_14") (pintype "output"))
    )
  )
)
